# HYDRA_V3_RECOVERY.net
KiCad netlist of a schematic drawn in Altium Designer
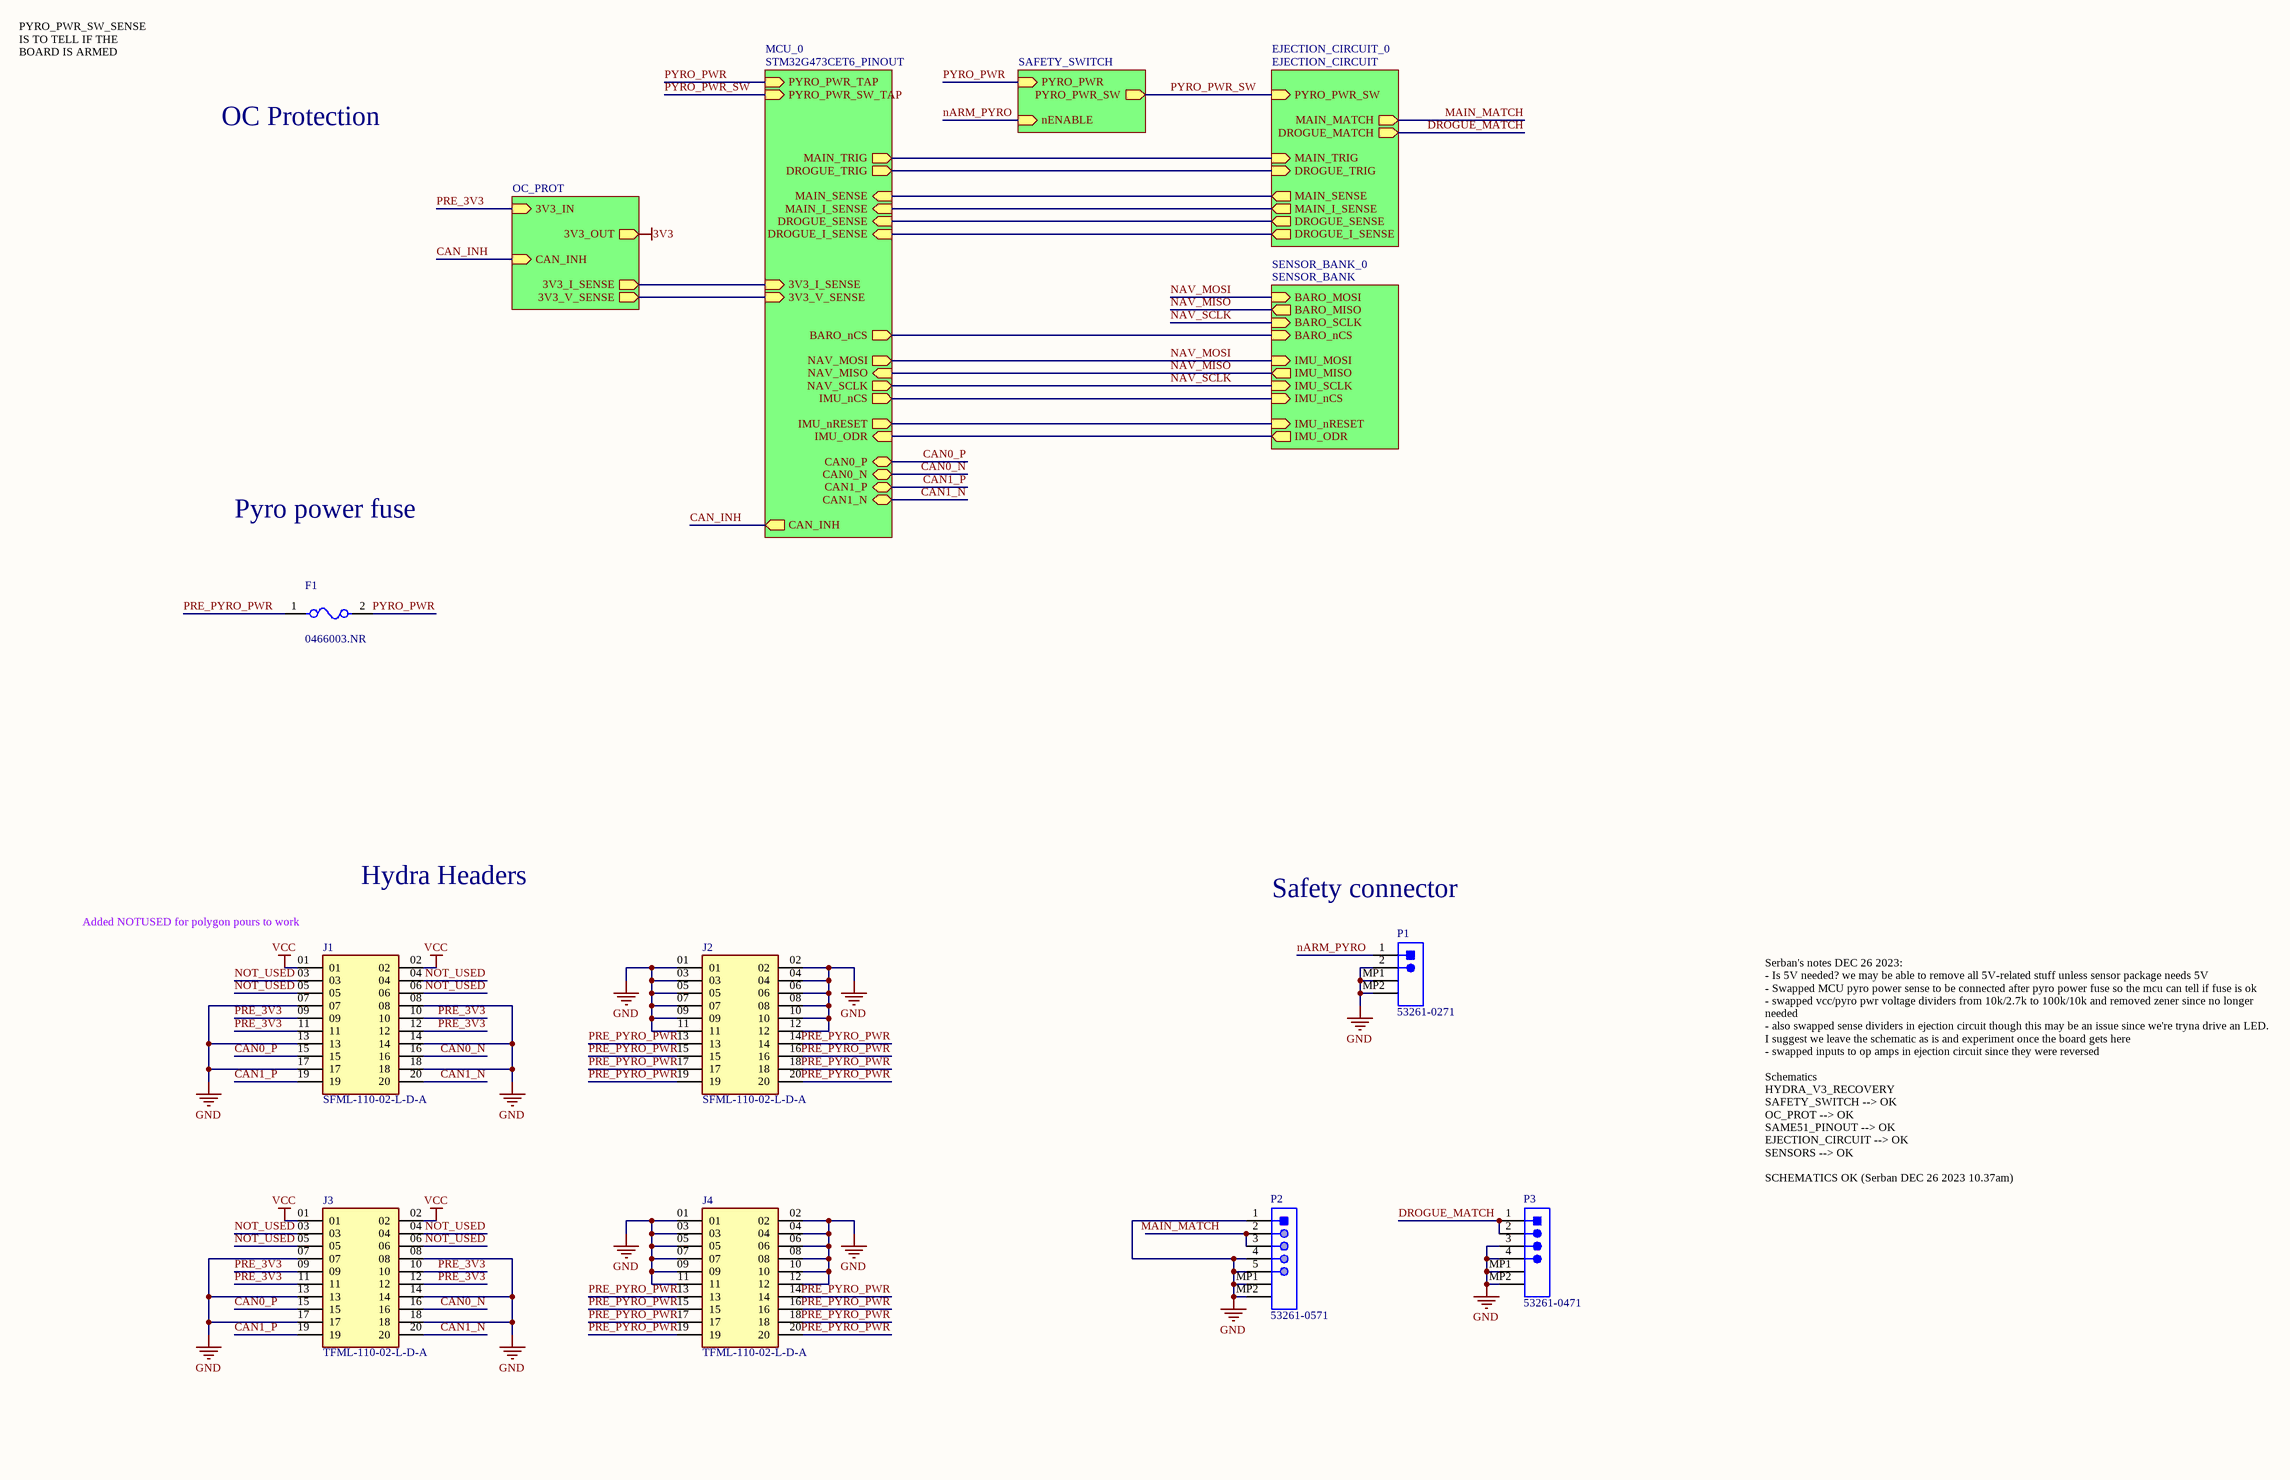
[diagram p0: HYDRA_V3_RECOVERY.SchDoc]

(export (version "E")
  (design (tool "Eeschema 10.0.6"))
  (components
    (comp (ref "F1")
      (value "0466003.NR")
      (footprint "FP-0466-MFG")
      (description "FUSE BOARD MNT 3A 32VAC/VDC 1206")
      (fields
        (field (name "OCTOPART") "https://octopart.com/0466003.nr-littelfuse-565175")
        (field (name "MANUFACTURER") "Littelfuse")
      )
      (libsource (lib "Altium Content Vault") (part "5bcf9b9f640e542cf0359d10258e979"))
    )
    (comp (ref "J1")
      (value "SFML-110-02-L-D-A")
      (footprint "SFML-110-02-L-D-A-Footprint-1")
      (libsource (lib "Space Concordia") (part "SFML-110-02-L-D-A"))
    )
    (comp (ref "J2")
      (value "SFML-110-02-L-D-A")
      (footprint "SFML-110-02-L-D-A-Footprint-1")
      (libsource (lib "Space Concordia") (part "SFML-110-02-L-D-A"))
    )
    (comp (ref "J3")
      (value "TFML-110-02-L-D-A")
      (footprint "TFML-110-02-L-D-A-Footprint-1")
      (description "Board Connector, 20 Contact(s), 2 Row(s), Male, Straight, Surface Mount Terminal")
      (libsource (lib "Space Concordia") (part "TFML-110-02-L-D-A"))
    )
    (comp (ref "J4")
      (value "TFML-110-02-L-D-A")
      (footprint "TFML-110-02-L-D-A-Footprint-1")
      (description "Board Connector, 20 Contact(s), 2 Row(s), Male, Straight, Surface Mount Terminal")
      (libsource (lib "Space Concordia") (part "TFML-110-02-L-D-A"))
    )
    (comp (ref "P1")
      (value "53261-0271")
      (footprint "MOLX-53261-0271_V")
      (description "PicoBlade(TM) Header, Right Angle, -40 to 85 degC, 2-Pin SMD, RoHS, Tape and Reel")
      (fields (field (name "MANUFACTURER") "Molex"))
      (libsource (lib "Altium Content Vault") (part "CN-1P-2M-R2"))
    )
    (comp (ref "P2")
      (value "53261-0571")
      (footprint "MOLX-52361-0571-5_V")
      (description "Male Header, Pitch 1.25 mm, 1 x 5 Position, Height 3.4 mm, RoHS, Tape and Reel")
      (fields (field (name "MANUFACTURER") "Molex"))
      (libsource (lib "Altium Content Vault") (part "CN-1P-2M-R5"))
    )
    (comp (ref "P3")
      (value "53261-0471")
      (footprint "MOLEX-53261-0471_V")
      (description "Male Header, Pitch 1.25 mm, 1 x 4 Position, Height 3.4 mm, -40 to 85 degC, RoHS, Tape and Reel")
      (fields (field (name "MANUFACTURER") "Molex"))
      (libsource (lib "Altium Content Vault") (part "CN-1P-2M-R4_A"))
    )
  )
  (nets
    (net (code "5") (name "/CAN0_N") (class "Default")
      (node (ref "J1") (pin "16") (pinfunction "16_16") (pintype "passive"))
      (node (ref "J3") (pin "16") (pinfunction "16_16") (pintype "passive"))
    )
    (net (code "6") (name "/CAN0_P") (class "Default")
      (node (ref "J1") (pin "15") (pinfunction "15_15") (pintype "passive"))
      (node (ref "J3") (pin "15") (pinfunction "15_15") (pintype "passive"))
    )
    (net (code "7") (name "/CAN1_N") (class "Default")
      (node (ref "J1") (pin "20") (pinfunction "20_20") (pintype "passive"))
      (node (ref "J3") (pin "20") (pinfunction "20_20") (pintype "passive"))
    )
    (net (code "8") (name "/CAN1_P") (class "Default")
      (node (ref "J1") (pin "19") (pinfunction "19_19") (pintype "passive"))
      (node (ref "J3") (pin "19") (pinfunction "19_19") (pintype "passive"))
    )
    (net (code "11") (name "/DROGUE_MATCH") (class "Default")
      (node (ref "P3") (pin "1") (pinfunction "1_1") (pintype "passive"))
      (node (ref "P3") (pin "2") (pinfunction "2_2") (pintype "passive"))
    )
    (net (code "18") (name "/MAIN_MATCH") (class "Default")
      (node (ref "P2") (pin "2") (pinfunction "2_2") (pintype "passive"))
      (node (ref "P2") (pin "3") (pinfunction "3_3") (pintype "passive"))
    )
    (net (code "24") (name "/NOT_USED") (class "Default")
      (node (ref "J1") (pin "03") (pinfunction "03_03") (pintype "passive"))
      (node (ref "J1") (pin "04") (pinfunction "04_04") (pintype "passive"))
      (node (ref "J1") (pin "05") (pinfunction "05_05") (pintype "passive"))
      (node (ref "J1") (pin "06") (pinfunction "06_06") (pintype "passive"))
      (node (ref "J3") (pin "03") (pinfunction "03_03") (pintype "passive"))
      (node (ref "J3") (pin "04") (pinfunction "04_04") (pintype "passive"))
      (node (ref "J3") (pin "05") (pinfunction "05_05") (pintype "passive"))
      (node (ref "J3") (pin "06") (pinfunction "06_06") (pintype "passive"))
    )
    (net (code "25") (name "/PRE_3V3") (class "Default")
      (node (ref "J1") (pin "09") (pinfunction "09_09") (pintype "passive"))
      (node (ref "J1") (pin "10") (pinfunction "10_10") (pintype "passive"))
      (node (ref "J1") (pin "11") (pinfunction "11_11") (pintype "passive"))
      (node (ref "J1") (pin "12") (pinfunction "12_12") (pintype "passive"))
      (node (ref "J3") (pin "09") (pinfunction "09_09") (pintype "passive"))
      (node (ref "J3") (pin "10") (pinfunction "10_10") (pintype "passive"))
      (node (ref "J3") (pin "11") (pinfunction "11_11") (pintype "passive"))
      (node (ref "J3") (pin "12") (pinfunction "12_12") (pintype "passive"))
    )
    (net (code "26") (name "/PRE_PYRO_PWR") (class "Default")
      (node (ref "F1") (pin "1") (pinfunction "1_1") (pintype "passive"))
      (node (ref "J2") (pin "13") (pinfunction "13_13") (pintype "passive"))
      (node (ref "J2") (pin "14") (pinfunction "14_14") (pintype "passive"))
      (node (ref "J2") (pin "15") (pinfunction "15_15") (pintype "passive"))
      (node (ref "J2") (pin "16") (pinfunction "16_16") (pintype "passive"))
      (node (ref "J2") (pin "17") (pinfunction "17_17") (pintype "passive"))
      (node (ref "J2") (pin "18") (pinfunction "18_18") (pintype "passive"))
      (node (ref "J2") (pin "19") (pinfunction "19_19") (pintype "passive"))
      (node (ref "J2") (pin "20") (pinfunction "20_20") (pintype "passive"))
      (node (ref "J4") (pin "13") (pinfunction "13_13") (pintype "passive"))
      (node (ref "J4") (pin "14") (pinfunction "14_14") (pintype "passive"))
      (node (ref "J4") (pin "15") (pinfunction "15_15") (pintype "passive"))
      (node (ref "J4") (pin "16") (pinfunction "16_16") (pintype "passive"))
      (node (ref "J4") (pin "17") (pinfunction "17_17") (pintype "passive"))
      (node (ref "J4") (pin "18") (pinfunction "18_18") (pintype "passive"))
      (node (ref "J4") (pin "19") (pinfunction "19_19") (pintype "passive"))
      (node (ref "J4") (pin "20") (pinfunction "20_20") (pintype "passive"))
    )
    (net (code "27") (name "/PYRO_PWR") (class "Default")
      (node (ref "F1") (pin "2") (pinfunction "2_2") (pintype "passive"))
    )
    (net (code "29") (name "/nARM_PYRO") (class "Default")
      (node (ref "P1") (pin "1") (pinfunction "1_1") (pintype "passive"))
    )
    (net (code "31") (name "GND") (class "Default")
      (node (ref "J1") (pin "07") (pinfunction "07_07") (pintype "passive"))
      (node (ref "J1") (pin "08") (pinfunction "08_08") (pintype "passive"))
      (node (ref "J1") (pin "13") (pinfunction "13_13") (pintype "passive"))
      (node (ref "J1") (pin "14") (pinfunction "14_14") (pintype "passive"))
      (node (ref "J1") (pin "17") (pinfunction "17_17") (pintype "passive"))
      (node (ref "J1") (pin "18") (pinfunction "18_18") (pintype "passive"))
      (node (ref "J2") (pin "01") (pinfunction "01_01") (pintype "passive"))
      (node (ref "J2") (pin "02") (pinfunction "02_02") (pintype "passive"))
      (node (ref "J2") (pin "03") (pinfunction "03_03") (pintype "passive"))
      (node (ref "J2") (pin "04") (pinfunction "04_04") (pintype "passive"))
      (node (ref "J2") (pin "05") (pinfunction "05_05") (pintype "passive"))
      (node (ref "J2") (pin "06") (pinfunction "06_06") (pintype "passive"))
      (node (ref "J2") (pin "07") (pinfunction "07_07") (pintype "passive"))
      (node (ref "J2") (pin "08") (pinfunction "08_08") (pintype "passive"))
      (node (ref "J2") (pin "09") (pinfunction "09_09") (pintype "passive"))
      (node (ref "J2") (pin "10") (pinfunction "10_10") (pintype "passive"))
      (node (ref "J2") (pin "11") (pinfunction "11_11") (pintype "passive"))
      (node (ref "J2") (pin "12") (pinfunction "12_12") (pintype "passive"))
      (node (ref "J3") (pin "07") (pinfunction "07_07") (pintype "passive"))
      (node (ref "J3") (pin "08") (pinfunction "08_08") (pintype "passive"))
      (node (ref "J3") (pin "13") (pinfunction "13_13") (pintype "passive"))
      (node (ref "J3") (pin "14") (pinfunction "14_14") (pintype "passive"))
      (node (ref "J3") (pin "17") (pinfunction "17_17") (pintype "passive"))
      (node (ref "J3") (pin "18") (pinfunction "18_18") (pintype "passive"))
      (node (ref "J4") (pin "01") (pinfunction "01_01") (pintype "passive"))
      (node (ref "J4") (pin "02") (pinfunction "02_02") (pintype "passive"))
      (node (ref "J4") (pin "03") (pinfunction "03_03") (pintype "passive"))
      (node (ref "J4") (pin "04") (pinfunction "04_04") (pintype "passive"))
      (node (ref "J4") (pin "05") (pinfunction "05_05") (pintype "passive"))
      (node (ref "J4") (pin "06") (pinfunction "06_06") (pintype "passive"))
      (node (ref "J4") (pin "07") (pinfunction "07_07") (pintype "passive"))
      (node (ref "J4") (pin "08") (pinfunction "08_08") (pintype "passive"))
      (node (ref "J4") (pin "09") (pinfunction "09_09") (pintype "passive"))
      (node (ref "J4") (pin "10") (pinfunction "10_10") (pintype "passive"))
      (node (ref "J4") (pin "11") (pinfunction "11_11") (pintype "passive"))
      (node (ref "J4") (pin "12") (pinfunction "12_12") (pintype "passive"))
      (node (ref "P1") (pin "2") (pinfunction "2_2") (pintype "passive"))
      (node (ref "P1") (pin "MP1") (pinfunction "MP1_MP1") (pintype "passive"))
      (node (ref "P1") (pin "MP2") (pinfunction "MP2_MP2") (pintype "passive"))
      (node (ref "P2") (pin "1") (pinfunction "1_1") (pintype "passive"))
      (node (ref "P2") (pin "4") (pinfunction "4_4") (pintype "passive"))
      (node (ref "P2") (pin "5") (pinfunction "5_5") (pintype "passive"))
      (node (ref "P2") (pin "MP1") (pinfunction "MP1_MP1") (pintype "passive"))
      (node (ref "P2") (pin "MP2") (pinfunction "MP2_MP2") (pintype "passive"))
      (node (ref "P3") (pin "3") (pinfunction "3_3") (pintype "passive"))
      (node (ref "P3") (pin "4") (pinfunction "4_4") (pintype "passive"))
      (node (ref "P3") (pin "MP1") (pinfunction "MP1_MP1") (pintype "passive"))
      (node (ref "P3") (pin "MP2") (pinfunction "MP2_MP2") (pintype "passive"))
    )
    (net (code "32") (name "VCC") (class "Default")
      (node (ref "J1") (pin "01") (pinfunction "01_01") (pintype "passive"))
      (node (ref "J1") (pin "02") (pinfunction "02_02") (pintype "passive"))
      (node (ref "J3") (pin "01") (pinfunction "01_01") (pintype "passive"))
      (node (ref "J3") (pin "02") (pinfunction "02_02") (pintype "passive"))
    )
  )
)
